# Sch_Power.net
KiCad netlist of a schematic drawn in Altium Designer
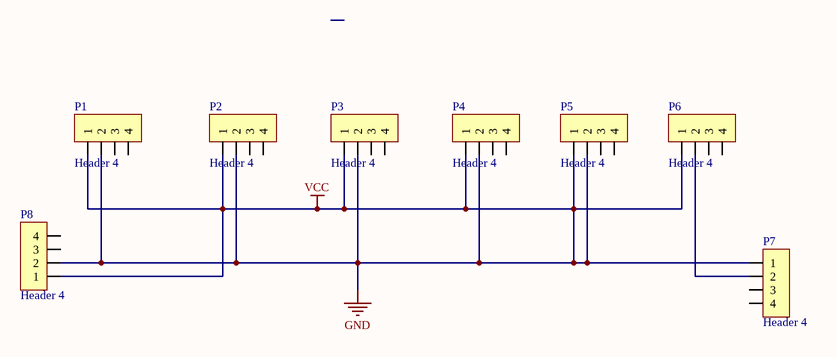
[diagram p0: Sch_Power.SchDoc]

(export (version "E")
  (design (tool "Eeschema 10.0.6"))
  (components
    (comp (ref "P1")
      (value "Header 4")
      (footprint "HDR/Header/4/BOX/SMD")
      (description "Header, 4-Pin")
      (libsource (lib "connectors") (part "Header 4"))
    )
    (comp (ref "P2")
      (value "Header 4")
      (footprint "HDR/Header/4/BOX/SMD")
      (description "Header, 4-Pin")
      (libsource (lib "connectors") (part "Header 4"))
    )
    (comp (ref "P3")
      (value "Header 4")
      (footprint "HDR/Header/4/BOX/SMD")
      (description "Header, 4-Pin")
      (libsource (lib "connectors") (part "Header 4"))
    )
    (comp (ref "P4")
      (value "Header 4")
      (footprint "HDR/Header/4/BOX/SMD")
      (description "Header, 4-Pin")
      (libsource (lib "connectors") (part "Header 4"))
    )
    (comp (ref "P5")
      (value "Header 4")
      (footprint "HDR/Header/4/BOX/SMD")
      (description "Header, 4-Pin")
      (libsource (lib "connectors") (part "Header 4"))
    )
    (comp (ref "P6")
      (value "Header 4")
      (footprint "HDR/Header/4/BOX/SMD")
      (description "Header, 4-Pin")
      (libsource (lib "connectors") (part "Header 4"))
    )
    (comp (ref "P7")
      (value "Header 4")
      (footprint "HDR/Header/4/BOX/SMD")
      (description "Header, 4-Pin")
      (libsource (lib "") (part "Header 4_2"))
    )
    (comp (ref "P8")
      (value "Header 4")
      (footprint "HDR/Header/4/BOX/SMD")
      (description "Header, 4-Pin")
      (libsource (lib "") (part "Header 4_1"))
    )
  )
  (nets
    (net (code "1") (name "GND") (class "Default")
      (node (ref "P1") (pin "1") (pinfunction "1_1") (pintype "passive"))
      (node (ref "P1") (pin "2") (pinfunction "2_2") (pintype "passive"))
      (node (ref "P2") (pin "1") (pinfunction "1_1") (pintype "passive"))
      (node (ref "P2") (pin "2") (pinfunction "2_2") (pintype "passive"))
      (node (ref "P3") (pin "1") (pinfunction "1_1") (pintype "passive"))
      (node (ref "P3") (pin "2") (pinfunction "2_2") (pintype "passive"))
      (node (ref "P4") (pin "1") (pinfunction "1_1") (pintype "passive"))
      (node (ref "P4") (pin "2") (pinfunction "2_2") (pintype "passive"))
      (node (ref "P5") (pin "1") (pinfunction "1_1") (pintype "passive"))
      (node (ref "P5") (pin "2") (pinfunction "2_2") (pintype "passive"))
      (node (ref "P6") (pin "1") (pinfunction "1_1") (pintype "passive"))
      (node (ref "P7") (pin "1") (pinfunction "1_1") (pintype "passive"))
      (node (ref "P8") (pin "1") (pinfunction "1_1") (pintype "passive"))
      (node (ref "P8") (pin "2") (pinfunction "2_2") (pintype "passive"))
    )
    (net (code "2") (name "Net-(P6-Pad2)") (class "Default")
      (node (ref "P6") (pin "2") (pinfunction "2_2") (pintype "passive"))
      (node (ref "P7") (pin "2") (pinfunction "2_2") (pintype "passive"))
    )
    (net (code "3") (name "unconnected-(P1-Pad3)") (class "Default")
      (node (ref "P1") (pin "3") (pinfunction "3_3") (pintype "passive"))
    )
    (net (code "4") (name "unconnected-(P1-Pad4)") (class "Default")
      (node (ref "P1") (pin "4") (pinfunction "4_4") (pintype "passive"))
    )
    (net (code "5") (name "unconnected-(P2-Pad3)") (class "Default")
      (node (ref "P2") (pin "3") (pinfunction "3_3") (pintype "passive"))
    )
    (net (code "6") (name "unconnected-(P2-Pad4)") (class "Default")
      (node (ref "P2") (pin "4") (pinfunction "4_4") (pintype "passive"))
    )
    (net (code "7") (name "unconnected-(P3-Pad3)") (class "Default")
      (node (ref "P3") (pin "3") (pinfunction "3_3") (pintype "passive"))
    )
    (net (code "8") (name "unconnected-(P3-Pad4)") (class "Default")
      (node (ref "P3") (pin "4") (pinfunction "4_4") (pintype "passive"))
    )
    (net (code "9") (name "unconnected-(P4-Pad3)") (class "Default")
      (node (ref "P4") (pin "3") (pinfunction "3_3") (pintype "passive"))
    )
    (net (code "10") (name "unconnected-(P4-Pad4)") (class "Default")
      (node (ref "P4") (pin "4") (pinfunction "4_4") (pintype "passive"))
    )
    (net (code "11") (name "unconnected-(P5-Pad3)") (class "Default")
      (node (ref "P5") (pin "3") (pinfunction "3_3") (pintype "passive"))
    )
    (net (code "12") (name "unconnected-(P5-Pad4)") (class "Default")
      (node (ref "P5") (pin "4") (pinfunction "4_4") (pintype "passive"))
    )
    (net (code "13") (name "unconnected-(P6-Pad3)") (class "Default")
      (node (ref "P6") (pin "3") (pinfunction "3_3") (pintype "passive"))
    )
    (net (code "14") (name "unconnected-(P6-Pad4)") (class "Default")
      (node (ref "P6") (pin "4") (pinfunction "4_4") (pintype "passive"))
    )
    (net (code "15") (name "unconnected-(P7-Pad3)") (class "Default")
      (node (ref "P7") (pin "3") (pinfunction "3_3") (pintype "passive"))
    )
    (net (code "16") (name "unconnected-(P7-Pad4)") (class "Default")
      (node (ref "P7") (pin "4") (pinfunction "4_4") (pintype "passive"))
    )
    (net (code "17") (name "unconnected-(P8-Pad3)") (class "Default")
      (node (ref "P8") (pin "3") (pinfunction "3_3") (pintype "passive"))
    )
    (net (code "18") (name "unconnected-(P8-Pad4)") (class "Default")
      (node (ref "P8") (pin "4") (pinfunction "4_4") (pintype "passive"))
    )
  )
)
